# ESP01-lights.net
KiCad netlist of a schematic drawn in EAGLE
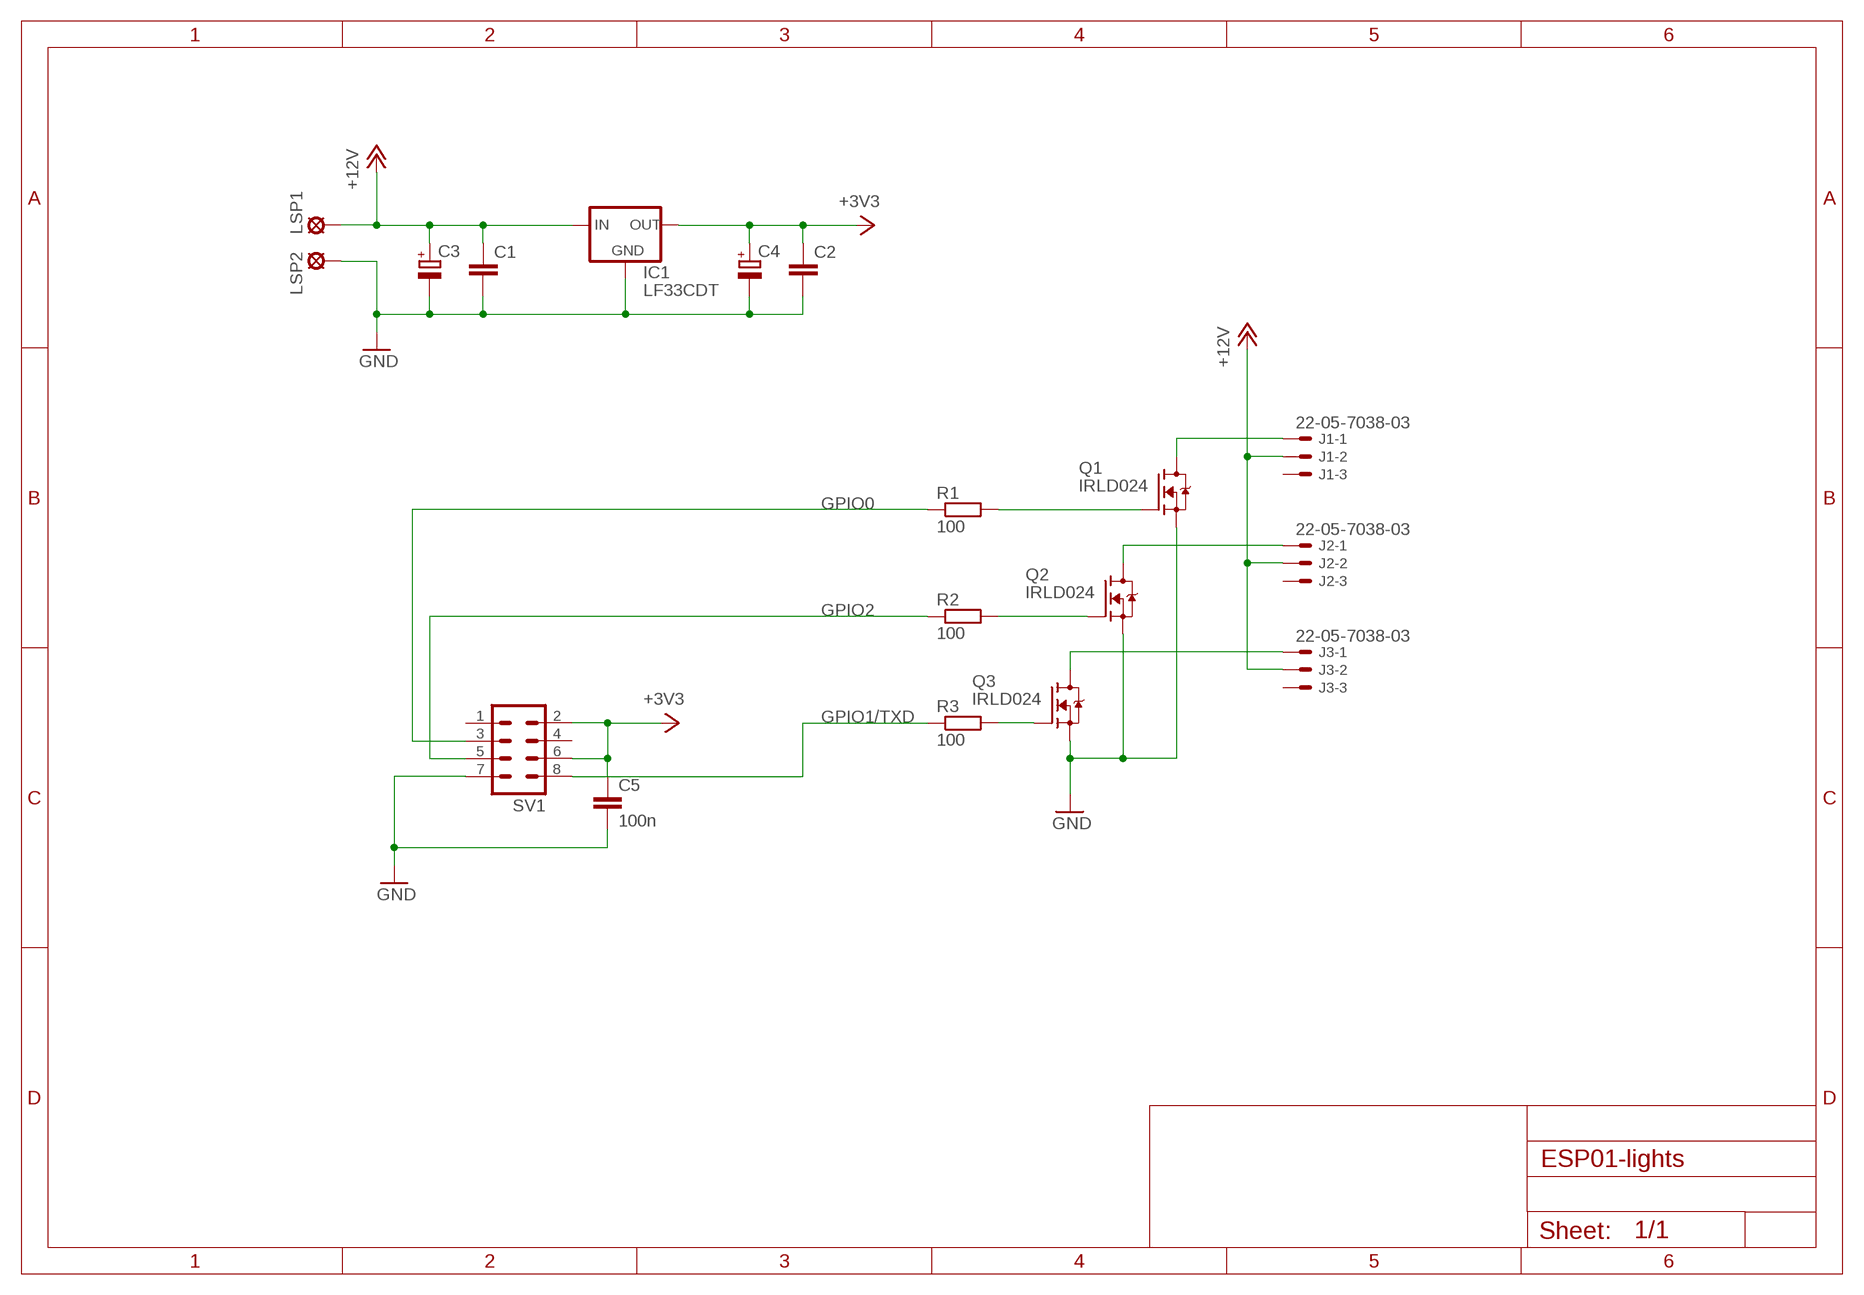
[diagram p0: schematic, sheet 1]

(export (version "E")
  (design (tool "Eeschema 10.0.6"))
  (components
    (comp (ref "C1")
      (value "C-EUC0805")
      (footprint "eagle-import:C0805")
      (libsource (lib "eagle-import") (part "C-EUC0805"))
    )
    (comp (ref "C2")
      (value "C-EUC0805")
      (footprint "eagle-import:C0805")
      (libsource (lib "eagle-import") (part "C-EUC0805"))
    )
    (comp (ref "C3")
      (value "CPOL-EUSMCA")
      (footprint "eagle-import:SMC_A")
      (libsource (lib "eagle-import") (part "CPOL-EUSMCA"))
    )
    (comp (ref "C4")
      (value "CPOL-EUSMCA")
      (footprint "eagle-import:SMC_A")
      (libsource (lib "eagle-import") (part "CPOL-EUSMCA"))
    )
    (comp (ref "C5")
      (value "100n")
      (footprint "eagle-import:C0805")
      (libsource (lib "eagle-import") (part "C-EUC0805"))
    )
    (comp (ref "IC1")
      (value "LF33CDT")
      (footprint "eagle-import:DPACK")
      (libsource (lib "eagle-import") (part "LP2950?CDT-3.3"))
    )
    (comp (ref "J1")
      (value "22-05-7038-03")
      (footprint "eagle-import:7395-03")
      (libsource (lib "eagle-import") (part "22-?-0305-7038"))
    )
    (comp (ref "J2")
      (value "22-05-7038-03")
      (footprint "eagle-import:7395-03")
      (libsource (lib "eagle-import") (part "22-?-0305-7038"))
    )
    (comp (ref "J3")
      (value "22-05-7038-03")
      (footprint "eagle-import:7395-03")
      (libsource (lib "eagle-import") (part "22-?-0305-7038"))
    )
    (comp (ref "LSP1")
      (value "LSP10")
      (footprint "eagle-import:LSP10")
      (libsource (lib "eagle-import") (part "LSP10"))
    )
    (comp (ref "LSP2")
      (value "LSP10")
      (footprint "eagle-import:LSP10")
      (libsource (lib "eagle-import") (part "LSP10"))
    )
    (comp (ref "Q1")
      (value "IRLD024")
      (footprint "eagle-import:P-TO247")
      (libsource (lib "eagle-import") (part "SPW47N60S5"))
    )
    (comp (ref "Q2")
      (value "IRLD024")
      (footprint "eagle-import:P-TO247")
      (libsource (lib "eagle-import") (part "SPW47N60S5"))
    )
    (comp (ref "Q3")
      (value "IRLD024")
      (footprint "eagle-import:P-TO247")
      (libsource (lib "eagle-import") (part "SPW47N60S5"))
    )
    (comp (ref "R1")
      (value "100")
      (footprint "eagle-import:0204V")
      (libsource (lib "eagle-import") (part "R-EU_0204/2V"))
    )
    (comp (ref "R2")
      (value "100")
      (footprint "eagle-import:0204V")
      (libsource (lib "eagle-import") (part "R-EU_0204/2V"))
    )
    (comp (ref "R3")
      (value "100")
      (footprint "eagle-import:0204V")
      (libsource (lib "eagle-import") (part "R-EU_0204/2V"))
    )
    (comp (ref "SV1")
      (value "MA04-2")
      (footprint "eagle-import:MA04-2")
      (libsource (lib "eagle-import") (part "MA04-2"))
    )
  )
  (nets
    (net (code "1") (name "+3V3") (class "Default")
      (node (ref "C2") (pin "1") (pinfunction "1_1") (pintype "passive"))
      (node (ref "C4") (pin "+") (pinfunction "+_+") (pintype "passive"))
      (node (ref "C5") (pin "1") (pinfunction "1_1") (pintype "passive"))
      (node (ref "IC1") (pin "3") (pinfunction "OUT_3") (pintype "passive"))
      (node (ref "SV1") (pin "2") (pinfunction "2_2") (pintype "passive"))
      (node (ref "SV1") (pin "6") (pinfunction "6_6") (pintype "passive"))
    )
    (net (code "2") (name "+12V") (class "Default")
      (node (ref "C1") (pin "1") (pinfunction "1_1") (pintype "passive"))
      (node (ref "C3") (pin "+") (pinfunction "+_+") (pintype "passive"))
      (node (ref "IC1") (pin "1") (pinfunction "IN_1") (pintype "input"))
      (node (ref "J1") (pin "2") (pinfunction "S_2") (pintype "passive"))
      (node (ref "J2") (pin "2") (pinfunction "S_2") (pintype "passive"))
      (node (ref "J3") (pin "2") (pinfunction "S_2") (pintype "passive"))
      (node (ref "LSP1") (pin "MP") (pinfunction "MP_MP") (pintype "passive"))
    )
    (net (code "3") (name "/GPIO0") (class "Default")
      (node (ref "R1") (pin "1") (pinfunction "1_1") (pintype "passive"))
      (node (ref "SV1") (pin "3") (pinfunction "3_3") (pintype "passive"))
    )
    (net (code "4") (name "/GPIO1{slash}TXD") (class "Default")
      (node (ref "R3") (pin "1") (pinfunction "1_1") (pintype "passive"))
      (node (ref "SV1") (pin "8") (pinfunction "8_8") (pintype "passive"))
    )
    (net (code "5") (name "/GPIO2") (class "Default")
      (node (ref "R2") (pin "1") (pinfunction "1_1") (pintype "passive"))
      (node (ref "SV1") (pin "5") (pinfunction "5_5") (pintype "passive"))
    )
    (net (code "6") (name "GND") (class "Default")
      (node (ref "C1") (pin "2") (pinfunction "2_2") (pintype "passive"))
      (node (ref "C2") (pin "2") (pinfunction "2_2") (pintype "passive"))
      (node (ref "C3") (pin "-") (pinfunction "-_-") (pintype "passive"))
      (node (ref "C4") (pin "-") (pinfunction "-_-") (pintype "passive"))
      (node (ref "C5") (pin "2") (pinfunction "2_2") (pintype "passive"))
      (node (ref "IC1") (pin "4") (pinfunction "GND_4") (pintype "input"))
      (node (ref "LSP2") (pin "MP") (pinfunction "MP_MP") (pintype "passive"))
      (node (ref "Q1") (pin "3") (pinfunction "S_3") (pintype "passive"))
      (node (ref "Q2") (pin "3") (pinfunction "S_3") (pintype "passive"))
      (node (ref "Q3") (pin "3") (pinfunction "S_3") (pintype "passive"))
      (node (ref "SV1") (pin "7") (pinfunction "7_7") (pintype "passive"))
    )
    (net (code "7") (name "Net-(J1A-S)") (class "Default")
      (node (ref "J1") (pin "1") (pinfunction "S_1") (pintype "passive"))
      (node (ref "Q1") (pin "2") (pinfunction "D_2") (pintype "passive"))
    )
    (net (code "8") (name "Net-(J2A-S)") (class "Default")
      (node (ref "J2") (pin "1") (pinfunction "S_1") (pintype "passive"))
      (node (ref "Q2") (pin "2") (pinfunction "D_2") (pintype "passive"))
    )
    (net (code "9") (name "Net-(J3A-S)") (class "Default")
      (node (ref "J3") (pin "1") (pinfunction "S_1") (pintype "passive"))
      (node (ref "Q3") (pin "2") (pinfunction "D_2") (pintype "passive"))
    )
    (net (code "10") (name "Net-(Q1-G)") (class "Default")
      (node (ref "Q1") (pin "1") (pinfunction "G_1") (pintype "passive"))
      (node (ref "R1") (pin "2") (pinfunction "2_2") (pintype "passive"))
    )
    (net (code "11") (name "Net-(Q2-G)") (class "Default")
      (node (ref "Q2") (pin "1") (pinfunction "G_1") (pintype "passive"))
      (node (ref "R2") (pin "2") (pinfunction "2_2") (pintype "passive"))
    )
    (net (code "12") (name "Net-(Q3-G)") (class "Default")
      (node (ref "Q3") (pin "1") (pinfunction "G_1") (pintype "passive"))
      (node (ref "R3") (pin "2") (pinfunction "2_2") (pintype "passive"))
    )
    (net (code "13") (name "unconnected-(J1C-S-Pad3)") (class "Default")
      (node (ref "J1") (pin "3") (pinfunction "S_3") (pintype "passive"))
    )
    (net (code "14") (name "unconnected-(J2C-S-Pad3)") (class "Default")
      (node (ref "J2") (pin "3") (pinfunction "S_3") (pintype "passive"))
    )
    (net (code "15") (name "unconnected-(J3C-S-Pad3)") (class "Default")
      (node (ref "J3") (pin "3") (pinfunction "S_3") (pintype "passive"))
    )
    (net (code "16") (name "unconnected-(SV1-Pad1)") (class "Default")
      (node (ref "SV1") (pin "1") (pinfunction "1_1") (pintype "passive"))
    )
    (net (code "17") (name "unconnected-(SV1-Pad4)") (class "Default")
      (node (ref "SV1") (pin "4") (pinfunction "4_4") (pintype "passive"))
    )
  )
)
